# power.net
KiCad netlist of a schematic drawn in EAGLE
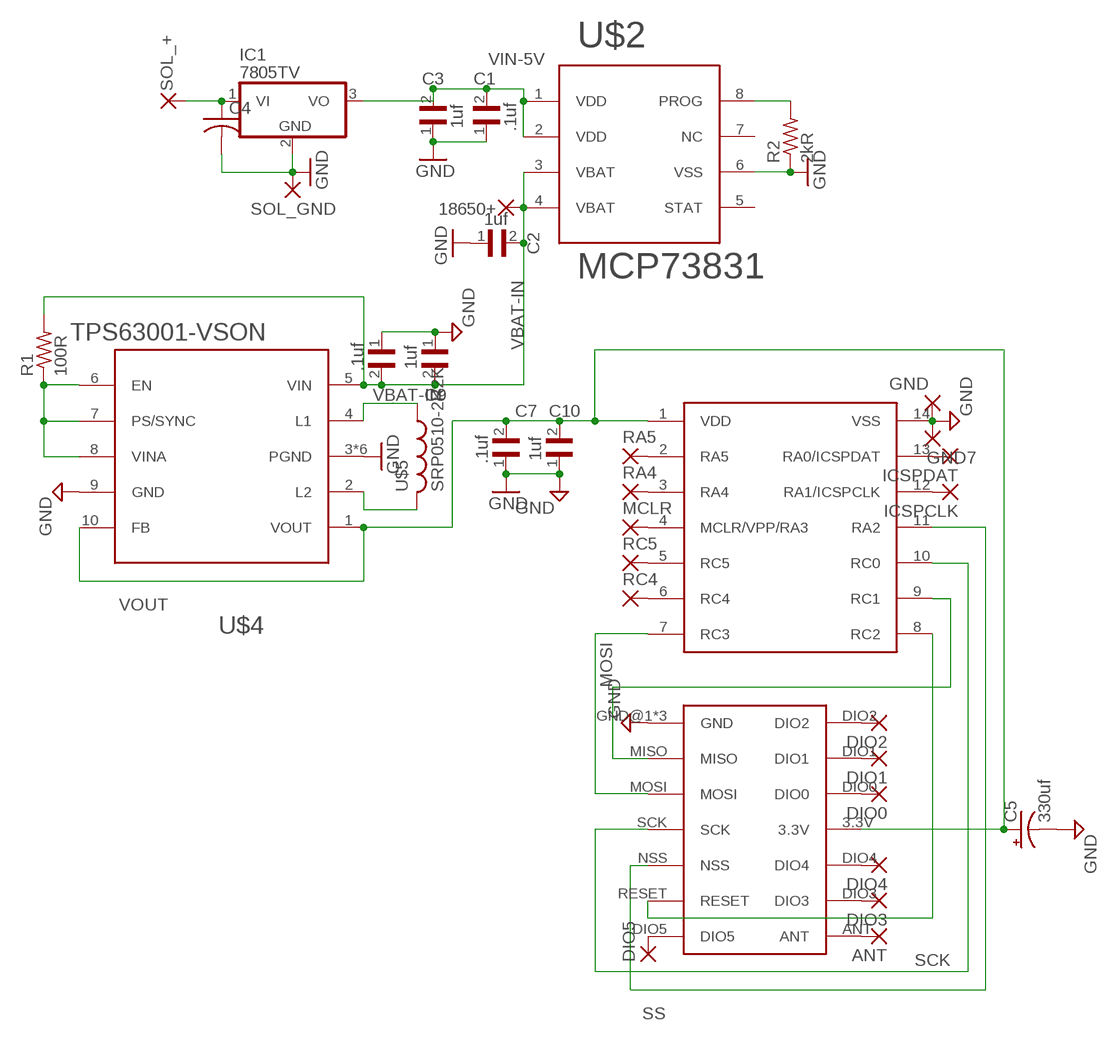
[diagram p0: schematic, sheet 1]

(export (version "E")
  (design (tool "Eeschema 10.0.6"))
  (components
    (comp (ref "18650+")
      (value "1,6/0,8")
      (footprint "eagle-import:1,6_0,8")
      (libsource (lib "eagle-import") (part "1,6/0,8"))
    )
    (comp (ref "ANT")
      (value "1,6/0,8")
      (footprint "eagle-import:1,6_0,8")
      (libsource (lib "eagle-import") (part "1,6/0,8"))
    )
    (comp (ref "C1")
      (value ".1uf")
      (footprint "eagle-import:CAPC1005X55N")
      (fields (field (name "MF") "Taiyo Yuden") (field (name "MP") "EMF105B7104MVHF"))
      (libsource (lib "eagle-import") (part "EMF105B7104MVHF"))
    )
    (comp (ref "C2")
      (value "1uf")
      (footprint "eagle-import:CAPC1005X70N")
      (fields (field (name "MF") "Taiyo Yuden") (field (name "MP") "UMK105CBJ105KV-F"))
      (libsource (lib "eagle-import") (part "UMK105CBJ105KV-F"))
    )
    (comp (ref "C3")
      (value "1uf")
      (footprint "eagle-import:CAPC1005X70N")
      (fields (field (name "MF") "Taiyo Yuden") (field (name "MP") "UMK105CBJ105KV-F"))
      (libsource (lib "eagle-import") (part "UMK105CBJ105KV-F"))
    )
    (comp (ref "C4")
      (value "C-USC0402")
      (footprint "eagle-import:C0402")
      (libsource (lib "eagle-import") (part "C-USC0402"))
    )
    (comp (ref "C5")
      (value "330uf")
      (footprint "eagle-import:E5-10,5")
      (libsource (lib "eagle-import") (part "CPOL-USE5-10.5"))
    )
    (comp (ref "C7")
      (value ".1uf")
      (footprint "eagle-import:CAPC1005X55N")
      (fields (field (name "MF") "Taiyo Yuden") (field (name "MP") "EMF105B7104MVHF"))
      (libsource (lib "eagle-import") (part "EMF105B7104MVHF"))
    )
    (comp (ref "C9")
      (value "1uf")
      (footprint "eagle-import:CAPC1005X70N")
      (fields (field (name "MF") "Taiyo Yuden") (field (name "MP") "UMK105CBJ105KV-F"))
      (libsource (lib "eagle-import") (part "UMK105CBJ105KV-F"))
    )
    (comp (ref "C10")
      (value "1uf")
      (footprint "eagle-import:CAPC1005X70N")
      (fields (field (name "MF") "Taiyo Yuden") (field (name "MP") "UMK105CBJ105KV-F"))
      (libsource (lib "eagle-import") (part "UMK105CBJ105KV-F"))
    )
    (comp (ref "DIO0")
      (value "1,6/0,8")
      (footprint "eagle-import:1,6_0,8")
      (libsource (lib "eagle-import") (part "1,6/0,8"))
    )
    (comp (ref "DIO1")
      (value "1,6/0,8")
      (footprint "eagle-import:1,6_0,8")
      (libsource (lib "eagle-import") (part "1,6/0,8"))
    )
    (comp (ref "DIO2")
      (value "1,6/0,8")
      (footprint "eagle-import:1,6_0,8")
      (libsource (lib "eagle-import") (part "1,6/0,8"))
    )
    (comp (ref "DIO3")
      (value "1,6/0,8")
      (footprint "eagle-import:1,6_0,8")
      (libsource (lib "eagle-import") (part "1,6/0,8"))
    )
    (comp (ref "DIO4")
      (value "1,6/0,8")
      (footprint "eagle-import:1,6_0,8")
      (libsource (lib "eagle-import") (part "1,6/0,8"))
    )
    (comp (ref "DIO5")
      (value "1,6/0,8")
      (footprint "eagle-import:1,6_0,8")
      (libsource (lib "eagle-import") (part "1,6/0,8"))
    )
    (comp (ref "GND")
      (value "1,6/0,8")
      (footprint "eagle-import:1,6_0,8")
      (libsource (lib "eagle-import") (part "1,6/0,8"))
    )
    (comp (ref "GND7")
      (value "1,6/0,8")
      (footprint "eagle-import:1,6_0,8")
      (libsource (lib "eagle-import") (part "1,6/0,8"))
    )
    (comp (ref "IC1")
      (value "7805TV")
      (footprint "eagle-import:TO220V")
      (libsource (lib "eagle-import") (part "78TV05"))
    )
    (comp (ref "ICSPCLK")
      (value "1,6/0,8")
      (footprint "eagle-import:1,6_0,8")
      (libsource (lib "eagle-import") (part "1,6/0,8"))
    )
    (comp (ref "ICSPDAT")
      (value "1,6/0,8")
      (footprint "eagle-import:1,6_0,8")
      (libsource (lib "eagle-import") (part "1,6/0,8"))
    )
    (comp (ref "MCLR")
      (value "1,6/0,8")
      (footprint "eagle-import:1,6_0,8")
      (libsource (lib "eagle-import") (part "1,6/0,8"))
    )
    (comp (ref "R1")
      (value "100R")
      (footprint "eagle-import:R0805")
      (libsource (lib "eagle-import") (part "R-US_R0805"))
    )
    (comp (ref "R2")
      (value "2kR")
      (footprint "eagle-import:0204_7")
      (libsource (lib "eagle-import") (part "R-US_0204/7"))
    )
    (comp (ref "RA4")
      (value "1,6/0,8")
      (footprint "eagle-import:1,6_0,8")
      (libsource (lib "eagle-import") (part "1,6/0,8"))
    )
    (comp (ref "RA5")
      (value "1,6/0,8")
      (footprint "eagle-import:1,6_0,8")
      (libsource (lib "eagle-import") (part "1,6/0,8"))
    )
    (comp (ref "RC4")
      (value "1,6/0,8")
      (footprint "eagle-import:1,6_0,8")
      (libsource (lib "eagle-import") (part "1,6/0,8"))
    )
    (comp (ref "RC5")
      (value "1,6/0,8")
      (footprint "eagle-import:1,6_0,8")
      (libsource (lib "eagle-import") (part "1,6/0,8"))
    )
    (comp (ref "SOL_+")
      (value "1,6/0,8")
      (footprint "eagle-import:1,6_0,8")
      (libsource (lib "eagle-import") (part "1,6/0,8"))
    )
    (comp (ref "SOL_GND")
      (value "1,6/0,8")
      (footprint "eagle-import:1,6_0,8")
      (libsource (lib "eagle-import") (part "1,6/0,8"))
    )
    (comp (ref "U$1")
      (value "PIC16F1615-TSSOP")
      (footprint "eagle-import:PIC16F(L)1615-TSSOP")
      (libsource (lib "eagle-import") (part "PIC16F1615-TSSOP"))
    )
    (comp (ref "U$2")
      (value "MCP73831")
      (footprint "eagle-import:MCP73831-DFN")
      (libsource (lib "eagle-import") (part "MCP73831"))
    )
    (comp (ref "U$3")
      (value "RFM69HCW")
      (footprint "eagle-import:RFM69HCW")
      (libsource (lib "eagle-import") (part "RFM69HCW"))
    )
    (comp (ref "U$4")
      (value "TPS63001-VSON")
      (footprint "eagle-import:TPS63001-VSON")
      (libsource (lib "eagle-import") (part "TPS63001-VSON"))
    )
    (comp (ref "U$5")
      (value "SRP0510-2R2K")
      (footprint "eagle-import:SRP0510-2R2K")
      (libsource (lib "eagle-import") (part "SRP0510-2R2K"))
    )
    (comp (ref "VBAT-IN")
      (value ".1uf")
      (footprint "eagle-import:CAPC1005X55N")
      (fields (field (name "MF") "Taiyo Yuden") (field (name "MP") "EMF105B7104MVHF"))
      (libsource (lib "eagle-import") (part "EMF105B7104MVHF"))
    )
  )
  (nets
    (net (code "1") (name "/MOSI") (class "Default")
      (node (ref "U$1") (pin "7") (pinfunction "RC3_7") (pintype "bidirectional"))
      (node (ref "U$3") (pin "MOSI") (pinfunction "MOSI_MOSI") (pintype "bidirectional"))
    )
    (net (code "2") (name "/SCK") (class "Default")
      (node (ref "U$1") (pin "10") (pinfunction "RC0_10") (pintype "bidirectional"))
      (node (ref "U$3") (pin "SCK") (pinfunction "SCK_SCK") (pintype "bidirectional"))
    )
    (net (code "3") (name "/SS") (class "Default")
      (node (ref "U$1") (pin "11") (pinfunction "RA2_11") (pintype "bidirectional"))
      (node (ref "U$3") (pin "NSS") (pinfunction "NSS_NSS") (pintype "bidirectional"))
    )
    (net (code "4") (name "/VBAT-IN") (class "Default")
      (node (ref "18650+") (pin "1") (pinfunction "P_1") (pintype "passive"))
      (node (ref "C2") (pin "2") (pinfunction "2_2") (pintype "passive"))
      (node (ref "C9") (pin "2") (pinfunction "2_2") (pintype "passive"))
      (node (ref "R1") (pin "2") (pinfunction "2_2") (pintype "passive"))
      (node (ref "U$2") (pin "3") (pinfunction "VBAT_3") (pintype "bidirectional"))
      (node (ref "U$2") (pin "4") (pinfunction "VBAT_4") (pintype "bidirectional"))
      (node (ref "U$4") (pin "5") (pinfunction "VIN_5") (pintype "bidirectional"))
      (node (ref "VBAT-IN") (pin "2") (pinfunction "2_2") (pintype "passive"))
    )
    (net (code "5") (name "/VIN-5V") (class "Default")
      (node (ref "C1") (pin "2") (pinfunction "2_2") (pintype "passive"))
      (node (ref "C3") (pin "2") (pinfunction "2_2") (pintype "passive"))
      (node (ref "IC1") (pin "3") (pinfunction "VO_3") (pintype "passive"))
      (node (ref "U$2") (pin "1") (pinfunction "VDD_1") (pintype "bidirectional"))
      (node (ref "U$2") (pin "2") (pinfunction "VDD_2") (pintype "bidirectional"))
    )
    (net (code "6") (name "/VOUT") (class "Default")
      (node (ref "C10") (pin "2") (pinfunction "2_2") (pintype "passive"))
      (node (ref "C5") (pin "+") (pinfunction "+_+") (pintype "passive"))
      (node (ref "C7") (pin "2") (pinfunction "2_2") (pintype "passive"))
      (node (ref "U$1") (pin "1") (pinfunction "VDD_1") (pintype "bidirectional"))
      (node (ref "U$3") (pin "3.3V") (pinfunction "3.3V_3.3V") (pintype "bidirectional"))
      (node (ref "U$4") (pin "1") (pinfunction "VOUT_1") (pintype "bidirectional"))
      (node (ref "U$4") (pin "10") (pinfunction "FB_10") (pintype "bidirectional"))
    )
    (net (code "7") (name "GND") (class "Default")
      (node (ref "C1") (pin "1") (pinfunction "1_1") (pintype "passive"))
      (node (ref "C10") (pin "1") (pinfunction "1_1") (pintype "passive"))
      (node (ref "C2") (pin "1") (pinfunction "1_1") (pintype "passive"))
      (node (ref "C3") (pin "1") (pinfunction "1_1") (pintype "passive"))
      (node (ref "C4") (pin "2") (pinfunction "2_2") (pintype "passive"))
      (node (ref "C5") (pin "-") (pinfunction "-_-") (pintype "passive"))
      (node (ref "C7") (pin "1") (pinfunction "1_1") (pintype "passive"))
      (node (ref "C9") (pin "1") (pinfunction "1_1") (pintype "passive"))
      (node (ref "GND") (pin "1") (pinfunction "P_1") (pintype "passive"))
      (node (ref "GND7") (pin "1") (pinfunction "P_1") (pintype "passive"))
      (node (ref "IC1") (pin "2") (pinfunction "GND_2") (pintype "passive"))
      (node (ref "R2") (pin "1") (pinfunction "1_1") (pintype "passive"))
      (node (ref "SOL_GND") (pin "1") (pinfunction "P_1") (pintype "passive"))
      (node (ref "U$1") (pin "14") (pinfunction "VSS_14") (pintype "bidirectional"))
      (node (ref "U$2") (pin "6") (pinfunction "VSS_6") (pintype "bidirectional"))
      (node (ref "U$3") (pin "GND@1") (pinfunction "GND_GND@1") (pintype "bidirectional"))
      (node (ref "U$3") (pin "GND@2") (pinfunction "GND_GND@2") (pintype "bidirectional"))
      (node (ref "U$3") (pin "GND@3") (pinfunction "GND_GND@3") (pintype "bidirectional"))
      (node (ref "U$4") (pin "11") (pinfunction "PGND_11") (pintype "bidirectional"))
      (node (ref "U$4") (pin "11@1") (pinfunction "PGND_11@1") (pintype "bidirectional"))
      (node (ref "U$4") (pin "11@2") (pinfunction "PGND_11@2") (pintype "bidirectional"))
      (node (ref "U$4") (pin "11@3") (pinfunction "PGND_11@3") (pintype "bidirectional"))
      (node (ref "U$4") (pin "11@4") (pinfunction "PGND_11@4") (pintype "bidirectional"))
      (node (ref "U$4") (pin "3") (pinfunction "PGND_3") (pintype "bidirectional"))
      (node (ref "U$4") (pin "9") (pinfunction "GND_9") (pintype "bidirectional"))
      (node (ref "VBAT-IN") (pin "1") (pinfunction "1_1") (pintype "passive"))
    )
    (net (code "8") (name "Net-(ANT-P)") (class "Default")
      (node (ref "ANT") (pin "1") (pinfunction "P_1") (pintype "passive"))
      (node (ref "U$3") (pin "ANT") (pinfunction "ANT_ANT") (pintype "bidirectional"))
    )
    (net (code "9") (name "Net-(DIO0-P)") (class "Default")
      (node (ref "DIO0") (pin "1") (pinfunction "P_1") (pintype "passive"))
      (node (ref "U$3") (pin "DIO0") (pinfunction "DIO0_DIO0") (pintype "bidirectional"))
    )
    (net (code "10") (name "Net-(DIO1-P)") (class "Default")
      (node (ref "DIO1") (pin "1") (pinfunction "P_1") (pintype "passive"))
      (node (ref "U$3") (pin "DIO1") (pinfunction "DIO1_DIO1") (pintype "bidirectional"))
    )
    (net (code "11") (name "Net-(DIO2-P)") (class "Default")
      (node (ref "DIO2") (pin "1") (pinfunction "P_1") (pintype "passive"))
      (node (ref "U$3") (pin "DIO2") (pinfunction "DIO2_DIO2") (pintype "bidirectional"))
    )
    (net (code "12") (name "Net-(DIO3-P)") (class "Default")
      (node (ref "DIO3") (pin "1") (pinfunction "P_1") (pintype "passive"))
      (node (ref "U$3") (pin "DIO3") (pinfunction "DIO3_DIO3") (pintype "bidirectional"))
    )
    (net (code "13") (name "Net-(DIO4-P)") (class "Default")
      (node (ref "DIO4") (pin "1") (pinfunction "P_1") (pintype "passive"))
      (node (ref "U$3") (pin "DIO4") (pinfunction "DIO4_DIO4") (pintype "bidirectional"))
    )
    (net (code "14") (name "Net-(DIO5-P)") (class "Default")
      (node (ref "DIO5") (pin "1") (pinfunction "P_1") (pintype "passive"))
      (node (ref "U$3") (pin "DIO5") (pinfunction "DIO5_DIO5") (pintype "bidirectional"))
    )
    (net (code "15") (name "Net-(IC1-VI)") (class "Default")
      (node (ref "C4") (pin "1") (pinfunction "1_1") (pintype "passive"))
      (node (ref "IC1") (pin "1") (pinfunction "VI_1") (pintype "input"))
      (node (ref "SOL_+") (pin "1") (pinfunction "P_1") (pintype "passive"))
    )
    (net (code "16") (name "Net-(ICSPCLK-P)") (class "Default")
      (node (ref "ICSPCLK") (pin "1") (pinfunction "P_1") (pintype "passive"))
      (node (ref "U$1") (pin "12") (pinfunction "RA1/ICSPCLK_12") (pintype "bidirectional"))
    )
    (net (code "17") (name "Net-(ICSPDAT-P)") (class "Default")
      (node (ref "ICSPDAT") (pin "1") (pinfunction "P_1") (pintype "passive"))
      (node (ref "U$1") (pin "13") (pinfunction "RA0/ICSPDAT_13") (pintype "bidirectional"))
    )
    (net (code "18") (name "Net-(MCLR-P)") (class "Default")
      (node (ref "MCLR") (pin "1") (pinfunction "P_1") (pintype "passive"))
      (node (ref "U$1") (pin "4") (pinfunction "MCLR/VPP/RA3_4") (pintype "bidirectional"))
    )
    (net (code "19") (name "Net-(RA4-P)") (class "Default")
      (node (ref "RA4") (pin "1") (pinfunction "P_1") (pintype "passive"))
      (node (ref "U$1") (pin "3") (pinfunction "RA4_3") (pintype "bidirectional"))
    )
    (net (code "20") (name "Net-(RA5-P)") (class "Default")
      (node (ref "RA5") (pin "1") (pinfunction "P_1") (pintype "passive"))
      (node (ref "U$1") (pin "2") (pinfunction "RA5_2") (pintype "bidirectional"))
    )
    (net (code "21") (name "Net-(RC4-P)") (class "Default")
      (node (ref "RC4") (pin "1") (pinfunction "P_1") (pintype "passive"))
      (node (ref "U$1") (pin "6") (pinfunction "RC4_6") (pintype "bidirectional"))
    )
    (net (code "22") (name "Net-(RC5-P)") (class "Default")
      (node (ref "RC5") (pin "1") (pinfunction "P_1") (pintype "passive"))
      (node (ref "U$1") (pin "5") (pinfunction "RC5_5") (pintype "bidirectional"))
    )
    (net (code "23") (name "Net-(U$1-RC1)") (class "Default")
      (node (ref "U$1") (pin "9") (pinfunction "RC1_9") (pintype "bidirectional"))
      (node (ref "U$3") (pin "MISO") (pinfunction "MISO_MISO") (pintype "bidirectional"))
    )
    (net (code "24") (name "Net-(U$1-RC2)") (class "Default")
      (node (ref "U$1") (pin "8") (pinfunction "RC2_8") (pintype "bidirectional"))
      (node (ref "U$3") (pin "RESET") (pinfunction "RESET_RESET") (pintype "bidirectional"))
    )
    (net (code "25") (name "Net-(U$2-PROG)") (class "Default")
      (node (ref "R2") (pin "2") (pinfunction "2_2") (pintype "passive"))
      (node (ref "U$2") (pin "8") (pinfunction "PROG_8") (pintype "bidirectional"))
    )
    (net (code "26") (name "Net-(U$4-EN)") (class "Default")
      (node (ref "R1") (pin "1") (pinfunction "1_1") (pintype "passive"))
      (node (ref "U$4") (pin "6") (pinfunction "EN_6") (pintype "bidirectional"))
      (node (ref "U$4") (pin "7") (pinfunction "PS/SYNC_7") (pintype "bidirectional"))
      (node (ref "U$4") (pin "8") (pinfunction "VINA_8") (pintype "bidirectional"))
    )
    (net (code "27") (name "Net-(U$4-L1)") (class "Default")
      (node (ref "U$4") (pin "4") (pinfunction "L1_4") (pintype "bidirectional"))
      (node (ref "U$5") (pin "P$1") (pinfunction "1_P$1") (pintype "passive"))
    )
    (net (code "28") (name "Net-(U$4-L2)") (class "Default")
      (node (ref "U$4") (pin "2") (pinfunction "L2_2") (pintype "bidirectional"))
      (node (ref "U$5") (pin "P$2") (pinfunction "2_P$2") (pintype "passive"))
    )
    (net (code "29") (name "unconnected-(U$2-NC-Pad7)") (class "Default")
      (node (ref "U$2") (pin "7") (pinfunction "NC_7") (pintype "bidirectional"))
    )
    (net (code "30") (name "unconnected-(U$2-STAT-Pad5)") (class "Default")
      (node (ref "U$2") (pin "5") (pinfunction "STAT_5") (pintype "bidirectional"))
    )
  )
)
